# nixie.net
KiCad netlist of a schematic drawn in EAGLE
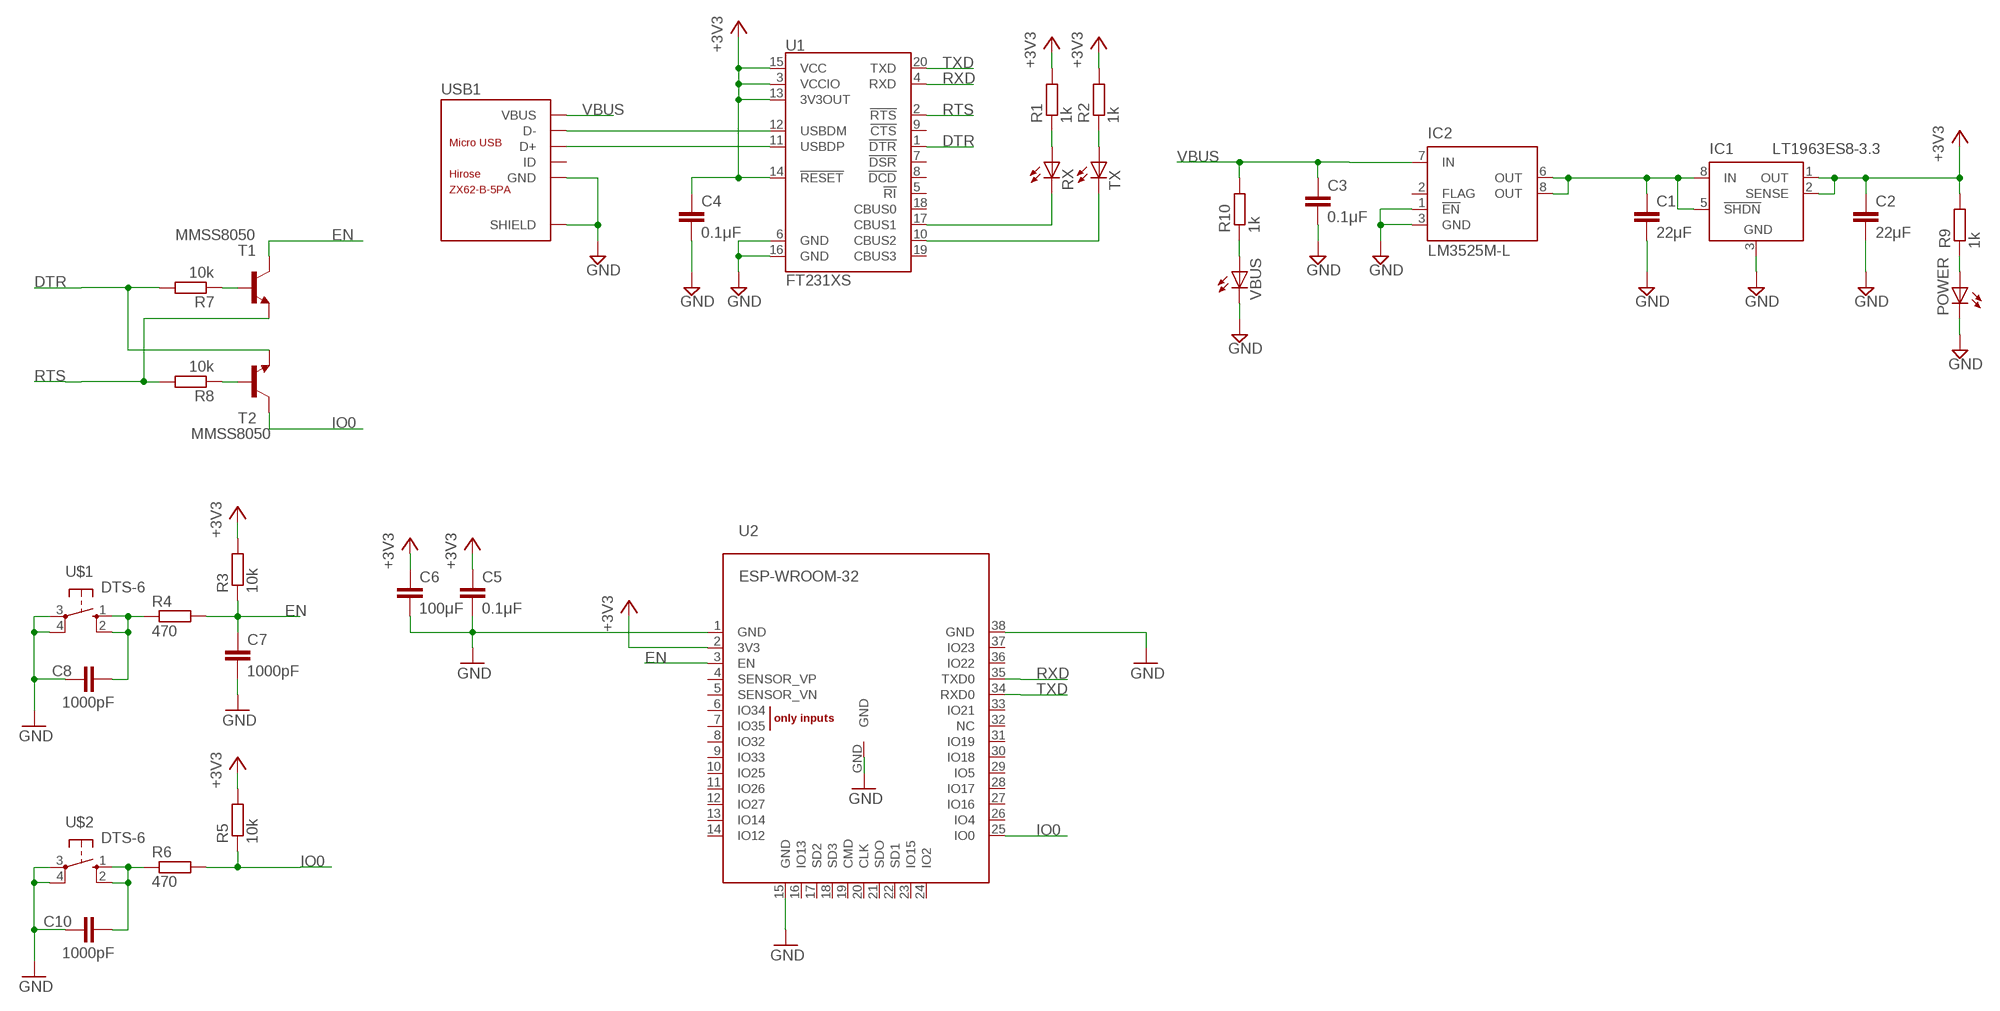
[diagram p0: schematic, sheet 1]

(export (version "E")
  (design (tool "Eeschema 10.0.6"))
  (components
    (comp (ref "C1")
      (value "22μF")
      (footprint "eagle-import:C2012")
      (libsource (lib "eagle-import") (part "resistor_348_C-EUC2012"))
    )
    (comp (ref "C2")
      (value "22μF")
      (footprint "eagle-import:C2012")
      (libsource (lib "eagle-import") (part "resistor_348_C-EUC2012"))
    )
    (comp (ref "C3")
      (value "0.1μF")
      (footprint "eagle-import:C0603")
      (libsource (lib "eagle-import") (part "C-EUC0603"))
    )
    (comp (ref "C4")
      (value "0.1μF")
      (footprint "eagle-import:C0603")
      (libsource (lib "eagle-import") (part "resistor_348_C-EUC0603"))
    )
    (comp (ref "C5")
      (value "0.1μF")
      (footprint "eagle-import:C0603")
      (libsource (lib "eagle-import") (part "resistor_348_C-EUC0603"))
    )
    (comp (ref "C6")
      (value "100μF")
      (footprint "eagle-import:C3225")
      (libsource (lib "eagle-import") (part "resistor_348_C-EUC3225"))
    )
    (comp (ref "C7")
      (value "1000pF")
      (footprint "eagle-import:C0603")
      (libsource (lib "eagle-import") (part "resistor_348_C-EUC0603"))
    )
    (comp (ref "C8")
      (value "1000pF")
      (footprint "eagle-import:C0603")
      (libsource (lib "eagle-import") (part "resistor_348_C-EUC0603"))
    )
    (comp (ref "C10")
      (value "1000pF")
      (footprint "eagle-import:C0603")
      (libsource (lib "eagle-import") (part "resistor_348_C-EUC0603"))
    )
    (comp (ref "IC1")
      (value "LT1963ES8-3.3")
      (footprint "eagle-import:SOIC8")
      (libsource (lib "eagle-import") (part "LT1963ES8-3.3"))
    )
    (comp (ref "IC2")
      (value "LM3525M-L")
      (footprint "eagle-import:SO08")
      (libsource (lib "eagle-import") (part "LM3525M-L"))
    )
    (comp (ref "POWER")
      (value "LEDCHIP-LED0603")
      (footprint "eagle-import:CHIP-LED0603")
      (libsource (lib "eagle-import") (part "LEDCHIP-LED0603"))
    )
    (comp (ref "R1")
      (value "1k")
      (footprint "eagle-import:R0603")
      (libsource (lib "eagle-import") (part "R-EU_R0603"))
    )
    (comp (ref "R2")
      (value "1k")
      (footprint "eagle-import:R0603")
      (libsource (lib "eagle-import") (part "R-EU_R0603"))
    )
    (comp (ref "R3")
      (value "10k")
      (footprint "eagle-import:R0603")
      (libsource (lib "eagle-import") (part "R-EU_R0603"))
    )
    (comp (ref "R4")
      (value "470")
      (footprint "eagle-import:R0603")
      (libsource (lib "eagle-import") (part "R-EU_R0603"))
    )
    (comp (ref "R5")
      (value "10k")
      (footprint "eagle-import:R0603")
      (libsource (lib "eagle-import") (part "R-EU_R0603"))
    )
    (comp (ref "R6")
      (value "470")
      (footprint "eagle-import:R0603")
      (libsource (lib "eagle-import") (part "R-EU_R0603"))
    )
    (comp (ref "R7")
      (value "10k")
      (footprint "eagle-import:R0603")
      (libsource (lib "eagle-import") (part "R-EU_R0603"))
    )
    (comp (ref "R8")
      (value "10k")
      (footprint "eagle-import:R0603")
      (libsource (lib "eagle-import") (part "R-EU_R0603"))
    )
    (comp (ref "R9")
      (value "1k")
      (footprint "eagle-import:R0603")
      (libsource (lib "eagle-import") (part "R-EU_R0603"))
    )
    (comp (ref "R10")
      (value "1k")
      (footprint "eagle-import:R0603")
      (libsource (lib "eagle-import") (part "R-EU_R0603"))
    )
    (comp (ref "RX")
      (value "LEDCHIP-LED0603")
      (footprint "eagle-import:CHIP-LED0603")
      (libsource (lib "eagle-import") (part "LEDCHIP-LED0603"))
    )
    (comp (ref "T1")
      (value "MMSS8050")
      (footprint "eagle-import:SOT23-EBC")
      (libsource (lib "eagle-import") (part "-NPN-SOT23-EBC"))
    )
    (comp (ref "T2")
      (value "MMSS8050")
      (footprint "eagle-import:SOT23-EBC")
      (libsource (lib "eagle-import") (part "-NPN-SOT23-EBC"))
    )
    (comp (ref "TX")
      (value "LEDCHIP-LED0603")
      (footprint "eagle-import:CHIP-LED0603")
      (libsource (lib "eagle-import") (part "LEDCHIP-LED0603"))
    )
    (comp (ref "U$1")
      (value "DTS-6")
      (footprint "eagle-import:DTS6")
      (libsource (lib "eagle-import") (part "DTS-6"))
    )
    (comp (ref "U$2")
      (value "DTS-6")
      (footprint "eagle-import:DTS6")
      (libsource (lib "eagle-import") (part "DTS-6"))
    )
    (comp (ref "U1")
      (value "FT231XS")
      (footprint "eagle-import:SSOP20_L")
      (libsource (lib "eagle-import") (part "FT231XS"))
    )
    (comp (ref "U2")
      (value "ESP-WROOM-32")
      (footprint "eagle-import:ESP-WROOM-32")
      (libsource (lib "eagle-import") (part "ESP-WROOM-32"))
    )
    (comp (ref "USB1")
      (value "ZX62-B-5PA")
      (footprint "eagle-import:MICRO-USB5+6P-SMD-0.65-AB")
      (libsource (lib "eagle-import") (part "MICRO-USB-SMD(ZX62-B-5PA)"))
    )
    (comp (ref "VBUS")
      (value "LEDCHIP-LED0603")
      (footprint "eagle-import:CHIP-LED0603")
      (libsource (lib "eagle-import") (part "LEDCHIP-LED0603"))
    )
  )
  (nets
    (net (code "1") (name "+3V3") (class "Default")
      (node (ref "C2") (pin "1") (pinfunction "1_1") (pintype "passive"))
      (node (ref "C4") (pin "1") (pinfunction "1_1") (pintype "passive"))
      (node (ref "C5") (pin "1") (pinfunction "1_1") (pintype "passive"))
      (node (ref "C6") (pin "1") (pinfunction "1_1") (pintype "passive"))
      (node (ref "IC1") (pin "1") (pinfunction "OUT_1") (pintype "output"))
      (node (ref "IC1") (pin "2") (pinfunction "SENSE_2") (pintype "input"))
      (node (ref "R1") (pin "2") (pinfunction "2_2") (pintype "passive"))
      (node (ref "R2") (pin "2") (pinfunction "2_2") (pintype "passive"))
      (node (ref "R3") (pin "2") (pinfunction "2_2") (pintype "passive"))
      (node (ref "R5") (pin "2") (pinfunction "2_2") (pintype "passive"))
      (node (ref "R9") (pin "2") (pinfunction "2_2") (pintype "passive"))
      (node (ref "U1") (pin "13") (pinfunction "3V3OUT_13") (pintype "bidirectional"))
      (node (ref "U1") (pin "14") (pinfunction "~{RESET}_14") (pintype "bidirectional"))
      (node (ref "U1") (pin "15") (pinfunction "VCC_15") (pintype "bidirectional"))
      (node (ref "U1") (pin "3") (pinfunction "VCCIO_3") (pintype "bidirectional"))
      (node (ref "U2") (pin "2") (pinfunction "3V3_2") (pintype "bidirectional"))
    )
    (net (code "2") (name "DTR") (class "Default")
      (node (ref "R7") (pin "2") (pinfunction "2_2") (pintype "passive"))
      (node (ref "T2") (pin "E") (pinfunction "E_E") (pintype "passive"))
      (node (ref "U1") (pin "1") (pinfunction "~{DTR}_1") (pintype "bidirectional"))
    )
    (net (code "3") (name "EN") (class "Default")
      (node (ref "C7") (pin "1") (pinfunction "1_1") (pintype "passive"))
      (node (ref "R3") (pin "1") (pinfunction "1_1") (pintype "passive"))
      (node (ref "R4") (pin "2") (pinfunction "2_2") (pintype "passive"))
      (node (ref "T1") (pin "C") (pinfunction "C_C") (pintype "passive"))
      (node (ref "U2") (pin "3") (pinfunction "EN_3") (pintype "bidirectional"))
    )
    (net (code "4") (name "GND") (class "Default")
      (node (ref "C1") (pin "2") (pinfunction "2_2") (pintype "passive"))
      (node (ref "C10") (pin "1") (pinfunction "1_1") (pintype "passive"))
      (node (ref "C2") (pin "2") (pinfunction "2_2") (pintype "passive"))
      (node (ref "C3") (pin "2") (pinfunction "2_2") (pintype "passive"))
      (node (ref "C4") (pin "2") (pinfunction "2_2") (pintype "passive"))
      (node (ref "C5") (pin "2") (pinfunction "2_2") (pintype "passive"))
      (node (ref "C6") (pin "2") (pinfunction "2_2") (pintype "passive"))
      (node (ref "C7") (pin "2") (pinfunction "2_2") (pintype "passive"))
      (node (ref "C8") (pin "1") (pinfunction "1_1") (pintype "passive"))
      (node (ref "IC1") (pin "3") (pinfunction "GND_3") (pintype "power_in"))
      (node (ref "IC2") (pin "1") (pinfunction "~{EN}_1") (pintype "input"))
      (node (ref "IC2") (pin "3") (pinfunction "GND_3") (pintype "power_in"))
      (node (ref "POWER") (pin "C") (pinfunction "C_C") (pintype "passive"))
      (node (ref "U$1") (pin "3") (pinfunction "P_3") (pintype "passive"))
      (node (ref "U$1") (pin "4") (pinfunction "P1_4") (pintype "passive"))
      (node (ref "U$2") (pin "3") (pinfunction "P_3") (pintype "passive"))
      (node (ref "U$2") (pin "4") (pinfunction "P1_4") (pintype "passive"))
      (node (ref "U1") (pin "16") (pinfunction "GND_16") (pintype "bidirectional"))
      (node (ref "U1") (pin "6") (pinfunction "GND_6") (pintype "bidirectional"))
      (node (ref "U2") (pin "1") (pinfunction "GND_1") (pintype "bidirectional"))
      (node (ref "U2") (pin "15") (pinfunction "GND_15") (pintype "bidirectional"))
      (node (ref "U2") (pin "38") (pinfunction "GND_38") (pintype "bidirectional"))
      (node (ref "U2") (pin "GND") (pinfunction "GND_GND") (pintype "bidirectional"))
      (node (ref "USB1") (pin "5") (pinfunction "GND_5") (pintype "power_in"))
      (node (ref "USB1") (pin "P1") (pinfunction "SHIELD_P1") (pintype "power_in"))
      (node (ref "USB1") (pin "P2") (pinfunction "SHIELD_P2") (pintype "power_in"))
      (node (ref "USB1") (pin "P3") (pinfunction "SHIELD_P3") (pintype "power_in"))
      (node (ref "USB1") (pin "P4") (pinfunction "SHIELD_P4") (pintype "power_in"))
      (node (ref "USB1") (pin "P5") (pinfunction "SHIELD_P5") (pintype "power_in"))
      (node (ref "USB1") (pin "P6") (pinfunction "SHIELD_P6") (pintype "power_in"))
      (node (ref "VBUS") (pin "C") (pinfunction "C_C") (pintype "passive"))
    )
    (net (code "5") (name "IO0") (class "Default")
      (node (ref "R5") (pin "1") (pinfunction "1_1") (pintype "passive"))
      (node (ref "R6") (pin "2") (pinfunction "2_2") (pintype "passive"))
      (node (ref "T2") (pin "C") (pinfunction "C_C") (pintype "passive"))
      (node (ref "U2") (pin "25") (pinfunction "IO0_25") (pintype "bidirectional"))
    )
    (net (code "6") (name "Net-(IC1A-IN)") (class "Default")
      (node (ref "C1") (pin "1") (pinfunction "1_1") (pintype "passive"))
      (node (ref "IC1") (pin "5") (pinfunction "~{SHDN}_5") (pintype "input"))
      (node (ref "IC1") (pin "8") (pinfunction "IN_8") (pintype "input"))
      (node (ref "IC2") (pin "6") (pinfunction "OUT_6") (pintype "output"))
      (node (ref "IC2") (pin "8") (pinfunction "OUT_8") (pintype "output"))
    )
    (net (code "7") (name "Net-(POWER-PadA)") (class "Default")
      (node (ref "POWER") (pin "A") (pinfunction "A_A") (pintype "passive"))
      (node (ref "R9") (pin "1") (pinfunction "1_1") (pintype "passive"))
    )
    (net (code "8") (name "Net-(R1-Pad1)") (class "Default")
      (node (ref "R1") (pin "1") (pinfunction "1_1") (pintype "passive"))
      (node (ref "RX") (pin "A") (pinfunction "A_A") (pintype "passive"))
    )
    (net (code "9") (name "Net-(R2-Pad1)") (class "Default")
      (node (ref "R2") (pin "1") (pinfunction "1_1") (pintype "passive"))
      (node (ref "TX") (pin "A") (pinfunction "A_A") (pintype "passive"))
    )
    (net (code "10") (name "Net-(R7-Pad1)") (class "Default")
      (node (ref "R7") (pin "1") (pinfunction "1_1") (pintype "passive"))
      (node (ref "T1") (pin "B") (pinfunction "B_B") (pintype "passive"))
    )
    (net (code "11") (name "Net-(R8-Pad1)") (class "Default")
      (node (ref "R8") (pin "1") (pinfunction "1_1") (pintype "passive"))
      (node (ref "T2") (pin "B") (pinfunction "B_B") (pintype "passive"))
    )
    (net (code "12") (name "Net-(R10-Pad1)") (class "Default")
      (node (ref "R10") (pin "1") (pinfunction "1_1") (pintype "passive"))
      (node (ref "VBUS") (pin "A") (pinfunction "A_A") (pintype "passive"))
    )
    (net (code "13") (name "Net-(U$1-S)") (class "Default")
      (node (ref "C8") (pin "2") (pinfunction "2_2") (pintype "passive"))
      (node (ref "R4") (pin "1") (pinfunction "1_1") (pintype "passive"))
      (node (ref "U$1") (pin "1") (pinfunction "S_1") (pintype "passive"))
      (node (ref "U$1") (pin "2") (pinfunction "S1_2") (pintype "passive"))
    )
    (net (code "14") (name "Net-(U$2-S)") (class "Default")
      (node (ref "C10") (pin "2") (pinfunction "2_2") (pintype "passive"))
      (node (ref "R6") (pin "1") (pinfunction "1_1") (pintype "passive"))
      (node (ref "U$2") (pin "1") (pinfunction "S_1") (pintype "passive"))
      (node (ref "U$2") (pin "2") (pinfunction "S1_2") (pintype "passive"))
    )
    (net (code "15") (name "Net-(U1-CBUS1)") (class "Default")
      (node (ref "RX") (pin "C") (pinfunction "C_C") (pintype "passive"))
      (node (ref "U1") (pin "17") (pinfunction "CBUS1_17") (pintype "bidirectional"))
    )
    (net (code "16") (name "Net-(U1-CBUS2)") (class "Default")
      (node (ref "TX") (pin "C") (pinfunction "C_C") (pintype "passive"))
      (node (ref "U1") (pin "10") (pinfunction "CBUS2_10") (pintype "bidirectional"))
    )
    (net (code "17") (name "Net-(U1-USBDM)") (class "Default")
      (node (ref "U1") (pin "12") (pinfunction "USBDM_12") (pintype "bidirectional"))
      (node (ref "USB1") (pin "2") (pinfunction "D-_2") (pintype "bidirectional"))
    )
    (net (code "18") (name "Net-(U1-USBDP)") (class "Default")
      (node (ref "U1") (pin "11") (pinfunction "USBDP_11") (pintype "bidirectional"))
      (node (ref "USB1") (pin "3") (pinfunction "D+_3") (pintype "bidirectional"))
    )
    (net (code "19") (name "RTS") (class "Default")
      (node (ref "R8") (pin "2") (pinfunction "2_2") (pintype "passive"))
      (node (ref "T1") (pin "E") (pinfunction "E_E") (pintype "passive"))
      (node (ref "U1") (pin "2") (pinfunction "~{RTS}_2") (pintype "bidirectional"))
    )
    (net (code "20") (name "RXD") (class "Default")
      (node (ref "U1") (pin "4") (pinfunction "RXD_4") (pintype "bidirectional"))
      (node (ref "U2") (pin "35") (pinfunction "TXD0_35") (pintype "bidirectional"))
    )
    (net (code "21") (name "TXD") (class "Default")
      (node (ref "U1") (pin "20") (pinfunction "TXD_20") (pintype "bidirectional"))
      (node (ref "U2") (pin "34") (pinfunction "RXD0_34") (pintype "bidirectional"))
    )
    (net (code "22") (name "VBUS") (class "Default")
      (node (ref "C3") (pin "1") (pinfunction "1_1") (pintype "passive"))
      (node (ref "IC2") (pin "7") (pinfunction "IN_7") (pintype "input"))
      (node (ref "R10") (pin "2") (pinfunction "2_2") (pintype "passive"))
      (node (ref "USB1") (pin "1") (pinfunction "VBUS_1") (pintype "power_in"))
    )
    (net (code "23") (name "unconnected-(IC2-FLAG-Pad2)") (class "Default")
      (node (ref "IC2") (pin "2") (pinfunction "FLAG_2") (pintype "output"))
    )
    (net (code "24") (name "unconnected-(IC2-NC-Pad4)") (class "Default")
      (node (ref "IC2") (pin "4") (pinfunction "NC_4") (pintype "no_connect"))
    )
    (net (code "25") (name "unconnected-(IC2-NC-Pad5)") (class "Default")
      (node (ref "IC2") (pin "5") (pinfunction "NC_5") (pintype "no_connect"))
    )
    (net (code "26") (name "unconnected-(U1-CBUS0-Pad18)") (class "Default")
      (node (ref "U1") (pin "18") (pinfunction "CBUS0_18") (pintype "bidirectional"))
    )
    (net (code "27") (name "unconnected-(U1-CBUS3-Pad19)") (class "Default")
      (node (ref "U1") (pin "19") (pinfunction "CBUS3_19") (pintype "bidirectional"))
    )
    (net (code "28") (name "unconnected-(U1-~{CTS}-Pad9)") (class "Default")
      (node (ref "U1") (pin "9") (pinfunction "~{CTS}_9") (pintype "bidirectional"))
    )
    (net (code "29") (name "unconnected-(U1-~{DCD}-Pad8)") (class "Default")
      (node (ref "U1") (pin "8") (pinfunction "~{DCD}_8") (pintype "bidirectional"))
    )
    (net (code "30") (name "unconnected-(U1-~{DSR}-Pad7)") (class "Default")
      (node (ref "U1") (pin "7") (pinfunction "~{DSR}_7") (pintype "bidirectional"))
    )
    (net (code "31") (name "unconnected-(U1-~{RI}-Pad5)") (class "Default")
      (node (ref "U1") (pin "5") (pinfunction "~{RI}_5") (pintype "bidirectional"))
    )
    (net (code "32") (name "unconnected-(U2-CLK-Pad20)") (class "Default")
      (node (ref "U2") (pin "20") (pinfunction "CLK_20") (pintype "bidirectional"))
    )
    (net (code "33") (name "unconnected-(U2-CMD-Pad19)") (class "Default")
      (node (ref "U2") (pin "19") (pinfunction "CMD_19") (pintype "bidirectional"))
    )
    (net (code "34") (name "unconnected-(U2-IO2-Pad24)") (class "Default")
      (node (ref "U2") (pin "24") (pinfunction "IO2_24") (pintype "bidirectional"))
    )
    (net (code "35") (name "unconnected-(U2-IO4-Pad26)") (class "Default")
      (node (ref "U2") (pin "26") (pinfunction "IO4_26") (pintype "bidirectional"))
    )
    (net (code "36") (name "unconnected-(U2-IO5-Pad29)") (class "Default")
      (node (ref "U2") (pin "29") (pinfunction "IO5_29") (pintype "bidirectional"))
    )
    (net (code "37") (name "unconnected-(U2-IO12-Pad14)") (class "Default")
      (node (ref "U2") (pin "14") (pinfunction "IO12_14") (pintype "bidirectional"))
    )
    (net (code "38") (name "unconnected-(U2-IO13-Pad16)") (class "Default")
      (node (ref "U2") (pin "16") (pinfunction "IO13_16") (pintype "bidirectional"))
    )
    (net (code "39") (name "unconnected-(U2-IO14-Pad13)") (class "Default")
      (node (ref "U2") (pin "13") (pinfunction "IO14_13") (pintype "bidirectional"))
    )
    (net (code "40") (name "unconnected-(U2-IO15-Pad23)") (class "Default")
      (node (ref "U2") (pin "23") (pinfunction "IO15_23") (pintype "bidirectional"))
    )
    (net (code "41") (name "unconnected-(U2-IO16-Pad27)") (class "Default")
      (node (ref "U2") (pin "27") (pinfunction "IO16_27") (pintype "bidirectional"))
    )
    (net (code "42") (name "unconnected-(U2-IO17-Pad28)") (class "Default")
      (node (ref "U2") (pin "28") (pinfunction "IO17_28") (pintype "bidirectional"))
    )
    (net (code "43") (name "unconnected-(U2-IO18-Pad30)") (class "Default")
      (node (ref "U2") (pin "30") (pinfunction "IO18_30") (pintype "bidirectional"))
    )
    (net (code "44") (name "unconnected-(U2-IO19-Pad31)") (class "Default")
      (node (ref "U2") (pin "31") (pinfunction "IO19_31") (pintype "bidirectional"))
    )
    (net (code "45") (name "unconnected-(U2-IO21-Pad33)") (class "Default")
      (node (ref "U2") (pin "33") (pinfunction "IO21_33") (pintype "bidirectional"))
    )
    (net (code "46") (name "unconnected-(U2-IO22-Pad36)") (class "Default")
      (node (ref "U2") (pin "36") (pinfunction "IO22_36") (pintype "bidirectional"))
    )
    (net (code "47") (name "unconnected-(U2-IO23-Pad37)") (class "Default")
      (node (ref "U2") (pin "37") (pinfunction "IO23_37") (pintype "bidirectional"))
    )
    (net (code "48") (name "unconnected-(U2-IO25-Pad10)") (class "Default")
      (node (ref "U2") (pin "10") (pinfunction "IO25_10") (pintype "bidirectional"))
    )
    (net (code "49") (name "unconnected-(U2-IO26-Pad11)") (class "Default")
      (node (ref "U2") (pin "11") (pinfunction "IO26_11") (pintype "bidirectional"))
    )
    (net (code "50") (name "unconnected-(U2-IO27-Pad12)") (class "Default")
      (node (ref "U2") (pin "12") (pinfunction "IO27_12") (pintype "bidirectional"))
    )
    (net (code "51") (name "unconnected-(U2-IO32-Pad8)") (class "Default")
      (node (ref "U2") (pin "8") (pinfunction "IO32_8") (pintype "bidirectional"))
    )
    (net (code "52") (name "unconnected-(U2-IO33-Pad9)") (class "Default")
      (node (ref "U2") (pin "9") (pinfunction "IO33_9") (pintype "bidirectional"))
    )
    (net (code "53") (name "unconnected-(U2-IO34-Pad6)") (class "Default")
      (node (ref "U2") (pin "6") (pinfunction "IO34_6") (pintype "input"))
    )
    (net (code "54") (name "unconnected-(U2-IO35-Pad7)") (class "Default")
      (node (ref "U2") (pin "7") (pinfunction "IO35_7") (pintype "input"))
    )
    (net (code "55") (name "unconnected-(U2-NC-Pad32)") (class "Default")
      (node (ref "U2") (pin "32") (pinfunction "NC_32") (pintype "bidirectional"))
    )
    (net (code "56") (name "unconnected-(U2-SD1-Pad22)") (class "Default")
      (node (ref "U2") (pin "22") (pinfunction "SD1_22") (pintype "bidirectional"))
    )
    (net (code "57") (name "unconnected-(U2-SD2-Pad17)") (class "Default")
      (node (ref "U2") (pin "17") (pinfunction "SD2_17") (pintype "bidirectional"))
    )
    (net (code "58") (name "unconnected-(U2-SD3-Pad18)") (class "Default")
      (node (ref "U2") (pin "18") (pinfunction "SD3_18") (pintype "bidirectional"))
    )
    (net (code "59") (name "unconnected-(U2-SDO-Pad21)") (class "Default")
      (node (ref "U2") (pin "21") (pinfunction "SDO_21") (pintype "bidirectional"))
    )
    (net (code "60") (name "unconnected-(U2-SENSOR_VN-Pad5)") (class "Default")
      (node (ref "U2") (pin "5") (pinfunction "SENSOR_VN_5") (pintype "input"))
    )
    (net (code "61") (name "unconnected-(U2-SENSOR_VP-Pad4)") (class "Default")
      (node (ref "U2") (pin "4") (pinfunction "SENSOR_VP_4") (pintype "input"))
    )
    (net (code "62") (name "unconnected-(USB1-ID-Pad4)") (class "Default")
      (node (ref "USB1") (pin "4") (pinfunction "ID_4") (pintype "bidirectional"))
    )
  )
)
